# VPThermo.net
KiCad netlist of a schematic drawn in EAGLE
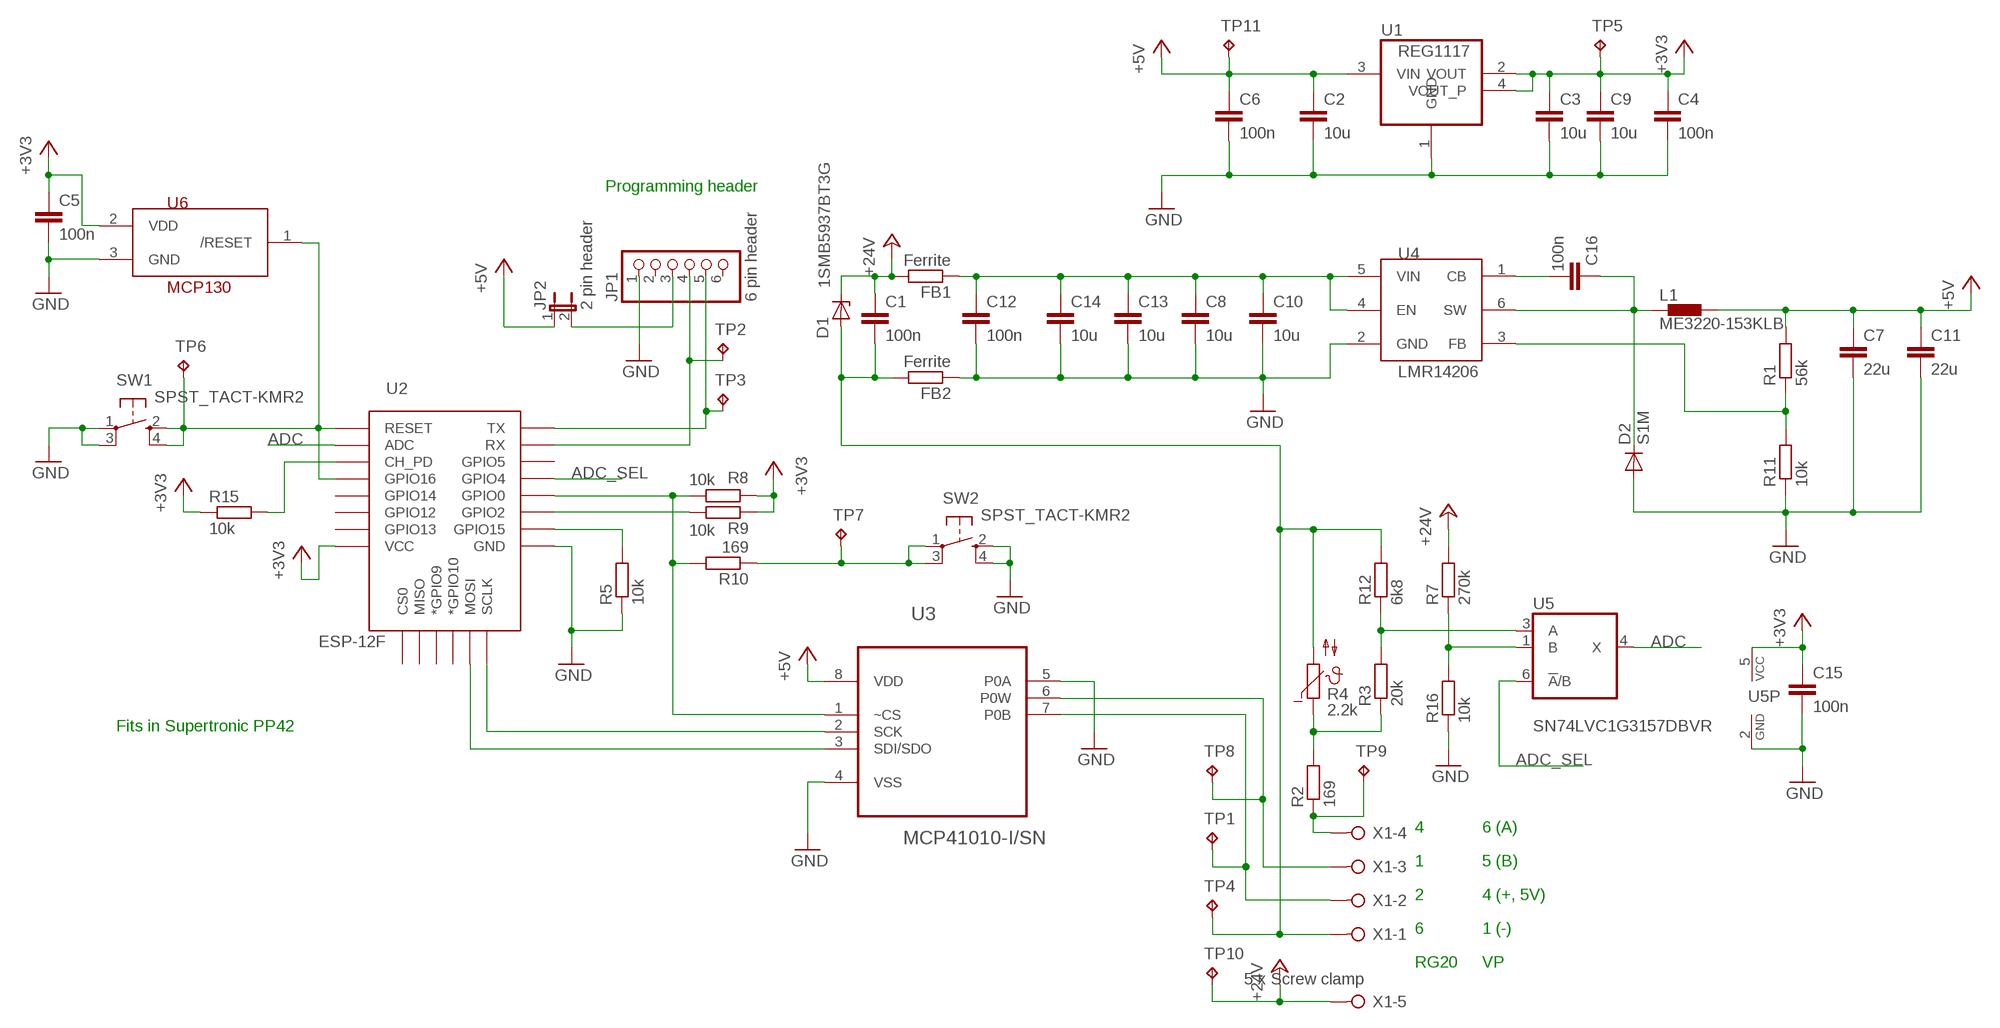
[diagram p0: schematic, sheet 1]

(export (version "E")
  (design (tool "Eeschema 10.0.6"))
  (components
    (comp (ref "C1")
      (value "100n")
      (footprint "eagle-import:C0603")
      (libsource (lib "eagle-import") (part "C-EUC0603"))
    )
    (comp (ref "C2")
      (value "10u")
      (footprint "eagle-import:C0805")
      (libsource (lib "eagle-import") (part "resistor_C-EUC0805"))
    )
    (comp (ref "C3")
      (value "10u")
      (footprint "eagle-import:C0805")
      (libsource (lib "eagle-import") (part "resistor_C-EUC0805"))
    )
    (comp (ref "C4")
      (value "100n")
      (footprint "eagle-import:C0603")
      (libsource (lib "eagle-import") (part "C-EUC0603"))
    )
    (comp (ref "C5")
      (value "100n")
      (footprint "eagle-import:C0603")
      (libsource (lib "eagle-import") (part "C-EUC0603"))
    )
    (comp (ref "C6")
      (value "100n")
      (footprint "eagle-import:C0603")
      (libsource (lib "eagle-import") (part "C-EUC0603"))
    )
    (comp (ref "C7")
      (value "22u")
      (footprint "eagle-import:C0805")
      (libsource (lib "eagle-import") (part "resistor_C-EUC0805"))
    )
    (comp (ref "C8")
      (value "10u")
      (footprint "eagle-import:C0805")
      (libsource (lib "eagle-import") (part "resistor_C-EUC0805"))
    )
    (comp (ref "C9")
      (value "10u")
      (footprint "eagle-import:C0805")
      (libsource (lib "eagle-import") (part "resistor_C-EUC0805"))
    )
    (comp (ref "C10")
      (value "10u")
      (footprint "eagle-import:C0805")
      (libsource (lib "eagle-import") (part "resistor_C-EUC0805"))
    )
    (comp (ref "C11")
      (value "22u")
      (footprint "eagle-import:C0805")
      (libsource (lib "eagle-import") (part "resistor_C-EUC0805"))
    )
    (comp (ref "C12")
      (value "100n")
      (footprint "eagle-import:C0603")
      (libsource (lib "eagle-import") (part "C-EUC0603"))
    )
    (comp (ref "C13")
      (value "10u")
      (footprint "eagle-import:C0805")
      (libsource (lib "eagle-import") (part "resistor_C-EUC0805"))
    )
    (comp (ref "C14")
      (value "10u")
      (footprint "eagle-import:C0805")
      (libsource (lib "eagle-import") (part "resistor_C-EUC0805"))
    )
    (comp (ref "C15")
      (value "100n")
      (footprint "eagle-import:C0603")
      (libsource (lib "eagle-import") (part "C-EUC0603"))
    )
    (comp (ref "C16")
      (value "100n")
      (footprint "eagle-import:C0603")
      (libsource (lib "eagle-import") (part "C-EUC0603"))
    )
    (comp (ref "D1")
      (value "1SMB5937BT3G")
      (footprint "eagle-import:SMB")
      (libsource (lib "eagle-import") (part "ZENER-DIODESMB"))
    )
    (comp (ref "D2")
      (value "S1M")
      (footprint "eagle-import:SMA")
      (libsource (lib "eagle-import") (part "S1M"))
    )
    (comp (ref "FB1")
      (value "Ferrite")
      (footprint "eagle-import:R0603")
      (libsource (lib "eagle-import") (part "RR0603"))
    )
    (comp (ref "FB2")
      (value "Ferrite")
      (footprint "eagle-import:R0603")
      (libsource (lib "eagle-import") (part "RR0603"))
    )
    (comp (ref "JP1")
      (value "6 pin header")
      (footprint "eagle-import:1X06")
      (libsource (lib "eagle-import") (part "PINHD-1X6"))
    )
    (comp (ref "JP2")
      (value "2 pin header")
      (footprint "eagle-import:JP1")
      (libsource (lib "eagle-import") (part "JP1E"))
    )
    (comp (ref "L1")
      (value "ME3220-153KLB")
      (footprint "eagle-import:SDR0302")
      (libsource (lib "eagle-import") (part "SDR0302"))
    )
    (comp (ref "R1")
      (value "56k")
      (footprint "eagle-import:R0603")
      (libsource (lib "eagle-import") (part "RR0603"))
    )
    (comp (ref "R2")
      (value "169")
      (footprint "eagle-import:R0603")
      (libsource (lib "eagle-import") (part "RR0603"))
    )
    (comp (ref "R3")
      (value "20k")
      (footprint "eagle-import:R0603")
      (libsource (lib "eagle-import") (part "RR0603"))
    )
    (comp (ref "R4")
      (value "2.2k")
      (footprint "eagle-import:P640")
      (fields (field (name "OC_FARNELL") "1187025"))
      (libsource (lib "eagle-import") (part "NTC640"))
    )
    (comp (ref "R5")
      (value "10k")
      (footprint "eagle-import:R0603")
      (libsource (lib "eagle-import") (part "RR0603"))
    )
    (comp (ref "R7")
      (value "270k")
      (footprint "eagle-import:R0603")
      (libsource (lib "eagle-import") (part "RR0603"))
    )
    (comp (ref "R8")
      (value "10k")
      (footprint "eagle-import:R0603")
      (libsource (lib "eagle-import") (part "RR0603"))
    )
    (comp (ref "R9")
      (value "10k")
      (footprint "eagle-import:R0603")
      (libsource (lib "eagle-import") (part "RR0603"))
    )
    (comp (ref "R10")
      (value "169")
      (footprint "eagle-import:R0603")
      (libsource (lib "eagle-import") (part "RR0603"))
    )
    (comp (ref "R11")
      (value "10k")
      (footprint "eagle-import:R0603")
      (libsource (lib "eagle-import") (part "RR0603"))
    )
    (comp (ref "R12")
      (value "6k8")
      (footprint "eagle-import:R0603")
      (libsource (lib "eagle-import") (part "RR0603"))
    )
    (comp (ref "R15")
      (value "10k")
      (footprint "eagle-import:R0603")
      (libsource (lib "eagle-import") (part "RR0603"))
    )
    (comp (ref "R16")
      (value "10k")
      (footprint "eagle-import:R0603")
      (libsource (lib "eagle-import") (part "RR0603"))
    )
    (comp (ref "SW1")
      (value "SPST_TACT-KMR2")
      (footprint "eagle-import:KMR2")
      (libsource (lib "eagle-import") (part "SPST_TACT-KMR2"))
    )
    (comp (ref "SW2")
      (value "SPST_TACT-KMR2")
      (footprint "eagle-import:KMR2")
      (libsource (lib "eagle-import") (part "SPST_TACT-KMR2"))
    )
    (comp (ref "TP1")
      (value "TPB1,27")
      (footprint "eagle-import:B1,27")
      (libsource (lib "eagle-import") (part "TPB1,27"))
    )
    (comp (ref "TP2")
      (value "TPB1,27")
      (footprint "eagle-import:B1,27")
      (libsource (lib "eagle-import") (part "TPB1,27"))
    )
    (comp (ref "TP3")
      (value "TPB1,27")
      (footprint "eagle-import:B1,27")
      (libsource (lib "eagle-import") (part "TPB1,27"))
    )
    (comp (ref "TP4")
      (value "TPB1,27")
      (footprint "eagle-import:B1,27")
      (libsource (lib "eagle-import") (part "TPB1,27"))
    )
    (comp (ref "TP5")
      (value "TPB1,27")
      (footprint "eagle-import:B1,27")
      (libsource (lib "eagle-import") (part "TPB1,27"))
    )
    (comp (ref "TP6")
      (value "TPB1,27")
      (footprint "eagle-import:B1,27")
      (libsource (lib "eagle-import") (part "TPB1,27"))
    )
    (comp (ref "TP7")
      (value "TPB1,27")
      (footprint "eagle-import:B1,27")
      (libsource (lib "eagle-import") (part "TPB1,27"))
    )
    (comp (ref "TP8")
      (value "TPB1,27")
      (footprint "eagle-import:B1,27")
      (libsource (lib "eagle-import") (part "TPB1,27"))
    )
    (comp (ref "TP9")
      (value "TPB1,27")
      (footprint "eagle-import:B1,27")
      (libsource (lib "eagle-import") (part "TPB1,27"))
    )
    (comp (ref "TP10")
      (value "TPB1,27")
      (footprint "eagle-import:B1,27")
      (libsource (lib "eagle-import") (part "TPB1,27"))
    )
    (comp (ref "TP11")
      (value "TPB1,27")
      (footprint "eagle-import:B1,27")
      (libsource (lib "eagle-import") (part "TPB1,27"))
    )
    (comp (ref "U1")
      (value "REG1117")
      (footprint "eagle-import:SOT223")
      (fields (field (name "OC_FARNELL") "1825376"))
      (libsource (lib "eagle-import") (part "REG1117"))
    )
    (comp (ref "U2")
      (value "ESP-12F")
      (footprint "eagle-import:ESP12E-SMD")
      (libsource (lib "eagle-import") (part "ESP12ESMD"))
    )
    (comp (ref "U3")
      (value "MCP41010-I/SN")
      (footprint "eagle-import:SOIC127P600X175-8N")
      (fields
        (field (name "MPN") "MCP4151-103E/SN")
        (field (name "MPN_1") "MCP41010-I/SN")
        (field (name "OC_FARNELL") "9758607")
      )
      (libsource (lib "eagle-import") (part "MCP4151-103E/SN"))
    )
    (comp (ref "U4")
      (value "LMR14206")
      (footprint "eagle-import:SOT-23-6")
      (libsource (lib "eagle-import") (part "LMR14206"))
    )
    (comp (ref "U5")
      (value "SN74LVC1G3157DBVR")
      (footprint "eagle-import:DBV_R-PDSO-G6")
      (fields (field (name "OC_FARNELL") "1470910"))
      (libsource (lib "eagle-import") (part "741G3157DBVR"))
    )
    (comp (ref "U6")
      (value "MCP130")
      (footprint "eagle-import:SOT23")
      (libsource (lib "eagle-import") (part "MCP130"))
    )
    (comp (ref "X1")
      (value "5 x Screw clamp")
      (footprint "eagle-import:W237-5P")
      (fields (field (name "OC_FARNELL") "1717004"))
      (libsource (lib "eagle-import") (part "W237-05P"))
    )
  )
  (nets
    (net (code "1") (name "+3V3") (class "Default")
      (node (ref "C15") (pin "1") (pinfunction "1_1") (pintype "passive"))
      (node (ref "C3") (pin "1") (pinfunction "1_1") (pintype "passive"))
      (node (ref "C4") (pin "1") (pinfunction "1_1") (pintype "passive"))
      (node (ref "C5") (pin "1") (pinfunction "1_1") (pintype "passive"))
      (node (ref "C9") (pin "1") (pinfunction "1_1") (pintype "passive"))
      (node (ref "R15") (pin "1") (pinfunction "1_1") (pintype "passive"))
      (node (ref "R8") (pin "1") (pinfunction "1_1") (pintype "passive"))
      (node (ref "R9") (pin "1") (pinfunction "1_1") (pintype "passive"))
      (node (ref "TP5") (pin "TP") (pinfunction "TP_TP") (pintype "input"))
      (node (ref "U1") (pin "2") (pinfunction "VOUT_2") (pintype "output"))
      (node (ref "U1") (pin "4") (pinfunction "VOUT_P_4") (pintype "output"))
      (node (ref "U2") (pin "VCC") (pinfunction "VCC_VCC") (pintype "bidirectional"))
      (node (ref "U5") (pin "5") (pinfunction "VCC_5") (pintype "power_in"))
      (node (ref "U6") (pin "2") (pinfunction "VDD_2") (pintype "power_in"))
    )
    (net (code "2") (name "+5V") (class "Default")
      (node (ref "C11") (pin "1") (pinfunction "1_1") (pintype "passive"))
      (node (ref "C2") (pin "1") (pinfunction "1_1") (pintype "passive"))
      (node (ref "C6") (pin "1") (pinfunction "1_1") (pintype "passive"))
      (node (ref "C7") (pin "1") (pinfunction "1_1") (pintype "passive"))
      (node (ref "JP2") (pin "1") (pinfunction "1_1") (pintype "passive"))
      (node (ref "L1") (pin "2") (pinfunction "2_2") (pintype "passive"))
      (node (ref "R1") (pin "2") (pinfunction "2_2") (pintype "passive"))
      (node (ref "TP11") (pin "TP") (pinfunction "TP_TP") (pintype "input"))
      (node (ref "U1") (pin "3") (pinfunction "VIN_3") (pintype "input"))
      (node (ref "U3") (pin "8") (pinfunction "VDD_8") (pintype "power_in"))
    )
    (net (code "3") (name "+24V") (class "Default")
      (node (ref "C1") (pin "1") (pinfunction "1_1") (pintype "passive"))
      (node (ref "D1") (pin "C") (pinfunction "C_C") (pintype "passive"))
      (node (ref "FB1") (pin "2") (pinfunction "2_2") (pintype "passive"))
      (node (ref "R7") (pin "2") (pinfunction "2_2") (pintype "passive"))
      (node (ref "TP10") (pin "TP") (pinfunction "TP_TP") (pintype "input"))
      (node (ref "X1") (pin "5") (pinfunction "KL_5") (pintype "passive"))
    )
    (net (code "4") (name "/ADC") (class "Default")
      (node (ref "U2") (pin "ADC") (pinfunction "ADC_ADC") (pintype "bidirectional"))
      (node (ref "U5") (pin "4") (pinfunction "X_4") (pintype "bidirectional"))
    )
    (net (code "5") (name "/ADC_SEL") (class "Default")
      (node (ref "U2") (pin "GPIO4") (pinfunction "GPIO4_GPIO4") (pintype "bidirectional"))
      (node (ref "U5") (pin "6") (pinfunction "~{A}/B_6") (pintype "input"))
    )
    (net (code "6") (name "GND") (class "Default")
      (node (ref "C10") (pin "2") (pinfunction "2_2") (pintype "passive"))
      (node (ref "C11") (pin "2") (pinfunction "2_2") (pintype "passive"))
      (node (ref "C12") (pin "2") (pinfunction "2_2") (pintype "passive"))
      (node (ref "C13") (pin "2") (pinfunction "2_2") (pintype "passive"))
      (node (ref "C14") (pin "2") (pinfunction "2_2") (pintype "passive"))
      (node (ref "C15") (pin "2") (pinfunction "2_2") (pintype "passive"))
      (node (ref "C2") (pin "2") (pinfunction "2_2") (pintype "passive"))
      (node (ref "C3") (pin "2") (pinfunction "2_2") (pintype "passive"))
      (node (ref "C4") (pin "2") (pinfunction "2_2") (pintype "passive"))
      (node (ref "C5") (pin "2") (pinfunction "2_2") (pintype "passive"))
      (node (ref "C6") (pin "2") (pinfunction "2_2") (pintype "passive"))
      (node (ref "C7") (pin "2") (pinfunction "2_2") (pintype "passive"))
      (node (ref "C8") (pin "2") (pinfunction "2_2") (pintype "passive"))
      (node (ref "C9") (pin "2") (pinfunction "2_2") (pintype "passive"))
      (node (ref "D2") (pin "A") (pinfunction "A_A") (pintype "passive"))
      (node (ref "FB2") (pin "1") (pinfunction "1_1") (pintype "passive"))
      (node (ref "JP1") (pin "1") (pinfunction "1_1") (pintype "passive"))
      (node (ref "R11") (pin "1") (pinfunction "1_1") (pintype "passive"))
      (node (ref "R16") (pin "1") (pinfunction "1_1") (pintype "passive"))
      (node (ref "R5") (pin "1") (pinfunction "1_1") (pintype "passive"))
      (node (ref "SW1") (pin "1") (pinfunction "P_1") (pintype "passive"))
      (node (ref "SW1") (pin "3") (pinfunction "P1_3") (pintype "passive"))
      (node (ref "SW2") (pin "2") (pinfunction "S_2") (pintype "passive"))
      (node (ref "SW2") (pin "4") (pinfunction "S1_4") (pintype "passive"))
      (node (ref "U1") (pin "1") (pinfunction "GND_1") (pintype "power_in"))
      (node (ref "U2") (pin "GND") (pinfunction "GND_GND") (pintype "bidirectional"))
      (node (ref "U3") (pin "4") (pinfunction "VSS_4") (pintype "passive"))
      (node (ref "U3") (pin "5") (pinfunction "P0A_5") (pintype "passive"))
      (node (ref "U4") (pin "2") (pinfunction "GND_2") (pintype "power_in"))
      (node (ref "U5") (pin "2") (pinfunction "GND_2") (pintype "power_in"))
      (node (ref "U6") (pin "3") (pinfunction "GND_3") (pintype "power_in"))
    )
    (net (code "7") (name "Net-(JP1-Pad3)") (class "Default")
      (node (ref "JP1") (pin "3") (pinfunction "3_3") (pintype "passive"))
      (node (ref "JP2") (pin "2") (pinfunction "2_2") (pintype "passive"))
    )
    (net (code "8") (name "Net-(R2-Pad2)") (class "Default")
      (node (ref "R2") (pin "2") (pinfunction "2_2") (pintype "passive"))
      (node (ref "R3") (pin "1") (pinfunction "1_1") (pintype "passive"))
      (node (ref "R4") (pin "1") (pinfunction "1_1") (pintype "passive"))
    )
    (net (code "9") (name "Net-(R5-Pad2)") (class "Default")
      (node (ref "R5") (pin "2") (pinfunction "2_2") (pintype "passive"))
      (node (ref "U2") (pin "GPIO15") (pinfunction "GPIO15_GPIO15") (pintype "bidirectional"))
    )
    (net (code "10") (name "Net-(R9-Pad2)") (class "Default")
      (node (ref "R9") (pin "2") (pinfunction "2_2") (pintype "passive"))
      (node (ref "U2") (pin "GPIO2") (pinfunction "GPIO2_GPIO2") (pintype "bidirectional"))
    )
    (net (code "11") (name "Net-(R15-Pad2)") (class "Default")
      (node (ref "R15") (pin "2") (pinfunction "2_2") (pintype "passive"))
      (node (ref "U2") (pin "CH_PD") (pinfunction "CH_PD_CH_PD") (pintype "bidirectional"))
    )
    (net (code "12") (name "Net-(SW1-S)") (class "Default")
      (node (ref "SW1") (pin "2") (pinfunction "S_2") (pintype "passive"))
      (node (ref "SW1") (pin "4") (pinfunction "S1_4") (pintype "passive"))
      (node (ref "TP6") (pin "TP") (pinfunction "TP_TP") (pintype "input"))
      (node (ref "U2") (pin "GPIO16") (pinfunction "GPIO16_GPIO16") (pintype "bidirectional"))
      (node (ref "U2") (pin "RESET") (pinfunction "RESET_RESET") (pintype "bidirectional"))
      (node (ref "U6") (pin "1") (pinfunction "/RESET_1") (pintype "open_collector"))
    )
    (net (code "13") (name "Net-(SW2-P)") (class "Default")
      (node (ref "R10") (pin "1") (pinfunction "1_1") (pintype "passive"))
      (node (ref "SW2") (pin "1") (pinfunction "P_1") (pintype "passive"))
      (node (ref "SW2") (pin "3") (pinfunction "P1_3") (pintype "passive"))
      (node (ref "TP7") (pin "TP") (pinfunction "TP_TP") (pintype "input"))
    )
    (net (code "14") (name "Net-(U2-RX)") (class "Default")
      (node (ref "JP1") (pin "4") (pinfunction "4_4") (pintype "passive"))
      (node (ref "TP2") (pin "TP") (pinfunction "TP_TP") (pintype "input"))
      (node (ref "U2") (pin "RXD0") (pinfunction "RX_RXD0") (pintype "bidirectional"))
    )
    (net (code "15") (name "Net-(U2-TX)") (class "Default")
      (node (ref "JP1") (pin "5") (pinfunction "5_5") (pintype "passive"))
      (node (ref "TP3") (pin "TP") (pinfunction "TP_TP") (pintype "input"))
      (node (ref "U2") (pin "TXD0") (pinfunction "TX_TXD0") (pintype "bidirectional"))
    )
    (net (code "16") (name "Net-(U3-P0B)") (class "Default")
      (node (ref "TP1") (pin "TP") (pinfunction "TP_TP") (pintype "input"))
      (node (ref "U3") (pin "7") (pinfunction "P0B_7") (pintype "passive"))
      (node (ref "X1") (pin "2") (pinfunction "KL_2") (pintype "passive"))
    )
    (net (code "17") (name "Net-(U3-P0W)") (class "Default")
      (node (ref "TP8") (pin "TP") (pinfunction "TP_TP") (pintype "input"))
      (node (ref "U3") (pin "6") (pinfunction "P0W_6") (pintype "passive"))
      (node (ref "X1") (pin "3") (pinfunction "KL_3") (pintype "passive"))
    )
    (net (code "18") (name "Net-(U3-SCK)") (class "Default")
      (node (ref "U2") (pin "SCLK") (pinfunction "SCLK_SCLK") (pintype "bidirectional"))
      (node (ref "U3") (pin "2") (pinfunction "SCK_2") (pintype "input"))
    )
    (net (code "19") (name "Net-(U3-SDI{slash}SDO)") (class "Default")
      (node (ref "U2") (pin "MOSI") (pinfunction "MOSI_MOSI") (pintype "bidirectional"))
      (node (ref "U3") (pin "3") (pinfunction "SDI/SDO_3") (pintype "bidirectional"))
    )
    (net (code "20") (name "Net-(U3-~{CS})") (class "Default")
      (node (ref "R10") (pin "2") (pinfunction "2_2") (pintype "passive"))
      (node (ref "R8") (pin "2") (pinfunction "2_2") (pintype "passive"))
      (node (ref "U2") (pin "GPIO0") (pinfunction "GPIO0_GPIO0") (pintype "bidirectional"))
      (node (ref "U3") (pin "1") (pinfunction "~{CS}_1") (pintype "input"))
    )
    (net (code "21") (name "Net-(U4-CB)") (class "Default")
      (node (ref "C16") (pin "2") (pinfunction "2_2") (pintype "passive"))
      (node (ref "U4") (pin "1") (pinfunction "CB_1") (pintype "power_in"))
    )
    (net (code "22") (name "Net-(U4-EN)") (class "Default")
      (node (ref "C10") (pin "1") (pinfunction "1_1") (pintype "passive"))
      (node (ref "C12") (pin "1") (pinfunction "1_1") (pintype "passive"))
      (node (ref "C13") (pin "1") (pinfunction "1_1") (pintype "passive"))
      (node (ref "C14") (pin "1") (pinfunction "1_1") (pintype "passive"))
      (node (ref "C8") (pin "1") (pinfunction "1_1") (pintype "passive"))
      (node (ref "FB1") (pin "1") (pinfunction "1_1") (pintype "passive"))
      (node (ref "U4") (pin "4") (pinfunction "EN_4") (pintype "input"))
      (node (ref "U4") (pin "5") (pinfunction "VIN_5") (pintype "power_in"))
    )
    (net (code "23") (name "Net-(U4-FB)") (class "Default")
      (node (ref "R1") (pin "1") (pinfunction "1_1") (pintype "passive"))
      (node (ref "R11") (pin "2") (pinfunction "2_2") (pintype "passive"))
      (node (ref "U4") (pin "3") (pinfunction "FB_3") (pintype "power_in"))
    )
    (net (code "24") (name "Net-(U4-SW)") (class "Default")
      (node (ref "C16") (pin "1") (pinfunction "1_1") (pintype "passive"))
      (node (ref "D2") (pin "C") (pinfunction "C_C") (pintype "passive"))
      (node (ref "L1") (pin "1") (pinfunction "1_1") (pintype "passive"))
      (node (ref "U4") (pin "6") (pinfunction "SW_6") (pintype "power_in"))
    )
    (net (code "25") (name "Net-(U5A-A)") (class "Default")
      (node (ref "R12") (pin "1") (pinfunction "1_1") (pintype "passive"))
      (node (ref "R3") (pin "2") (pinfunction "2_2") (pintype "passive"))
      (node (ref "U5") (pin "3") (pinfunction "A_3") (pintype "bidirectional"))
    )
    (net (code "26") (name "Net-(U5A-B)") (class "Default")
      (node (ref "R16") (pin "2") (pinfunction "2_2") (pintype "passive"))
      (node (ref "R7") (pin "1") (pinfunction "1_1") (pintype "passive"))
      (node (ref "U5") (pin "1") (pinfunction "B_1") (pintype "bidirectional"))
    )
    (net (code "27") (name "Net-(X1A-KL)") (class "Default")
      (node (ref "C1") (pin "2") (pinfunction "2_2") (pintype "passive"))
      (node (ref "D1") (pin "A") (pinfunction "A_A") (pintype "passive"))
      (node (ref "FB2") (pin "2") (pinfunction "2_2") (pintype "passive"))
      (node (ref "R12") (pin "2") (pinfunction "2_2") (pintype "passive"))
      (node (ref "R4") (pin "2") (pinfunction "2_2") (pintype "passive"))
      (node (ref "TP4") (pin "TP") (pinfunction "TP_TP") (pintype "input"))
      (node (ref "X1") (pin "1") (pinfunction "KL_1") (pintype "passive"))
    )
    (net (code "28") (name "Net-(X1D-KL)") (class "Default")
      (node (ref "R2") (pin "1") (pinfunction "1_1") (pintype "passive"))
      (node (ref "TP9") (pin "TP") (pinfunction "TP_TP") (pintype "input"))
      (node (ref "X1") (pin "4") (pinfunction "KL_4") (pintype "passive"))
    )
    (net (code "29") (name "unconnected-(JP1-Pad2)") (class "Default")
      (node (ref "JP1") (pin "2") (pinfunction "2_2") (pintype "passive"))
    )
    (net (code "30") (name "unconnected-(JP1-Pad6)") (class "Default")
      (node (ref "JP1") (pin "6") (pinfunction "6_6") (pintype "passive"))
    )
    (net (code "31") (name "unconnected-(U2-*GPIO9-PadGPIO9)") (class "Default")
      (node (ref "U2") (pin "GPIO9") (pinfunction "*GPIO9_GPIO9") (pintype "bidirectional"))
    )
    (net (code "32") (name "unconnected-(U2-*GPIO10-PadGPIO10)") (class "Default")
      (node (ref "U2") (pin "GPIO10") (pinfunction "*GPIO10_GPIO10") (pintype "bidirectional"))
    )
    (net (code "33") (name "unconnected-(U2-PadCS0)") (class "Default")
      (node (ref "U2") (pin "CS0") (pinfunction "CS0_CS0") (pintype "bidirectional"))
    )
    (net (code "34") (name "unconnected-(U2-PadGPIO5)") (class "Default")
      (node (ref "U2") (pin "GPIO5") (pinfunction "GPIO5_GPIO5") (pintype "bidirectional"))
    )
    (net (code "35") (name "unconnected-(U2-PadGPIO12)") (class "Default")
      (node (ref "U2") (pin "GPIO12") (pinfunction "GPIO12_GPIO12") (pintype "bidirectional"))
    )
    (net (code "36") (name "unconnected-(U2-PadGPIO13)") (class "Default")
      (node (ref "U2") (pin "GPIO13") (pinfunction "GPIO13_GPIO13") (pintype "bidirectional"))
    )
    (net (code "37") (name "unconnected-(U2-PadGPIO14)") (class "Default")
      (node (ref "U2") (pin "GPIO14") (pinfunction "GPIO14_GPIO14") (pintype "bidirectional"))
    )
    (net (code "38") (name "unconnected-(U2-PadMISO)") (class "Default")
      (node (ref "U2") (pin "MISO") (pinfunction "MISO_MISO") (pintype "bidirectional"))
    )
  )
)
